# input1-9.net
KiCad netlist of a schematic drawn in Altium Designer
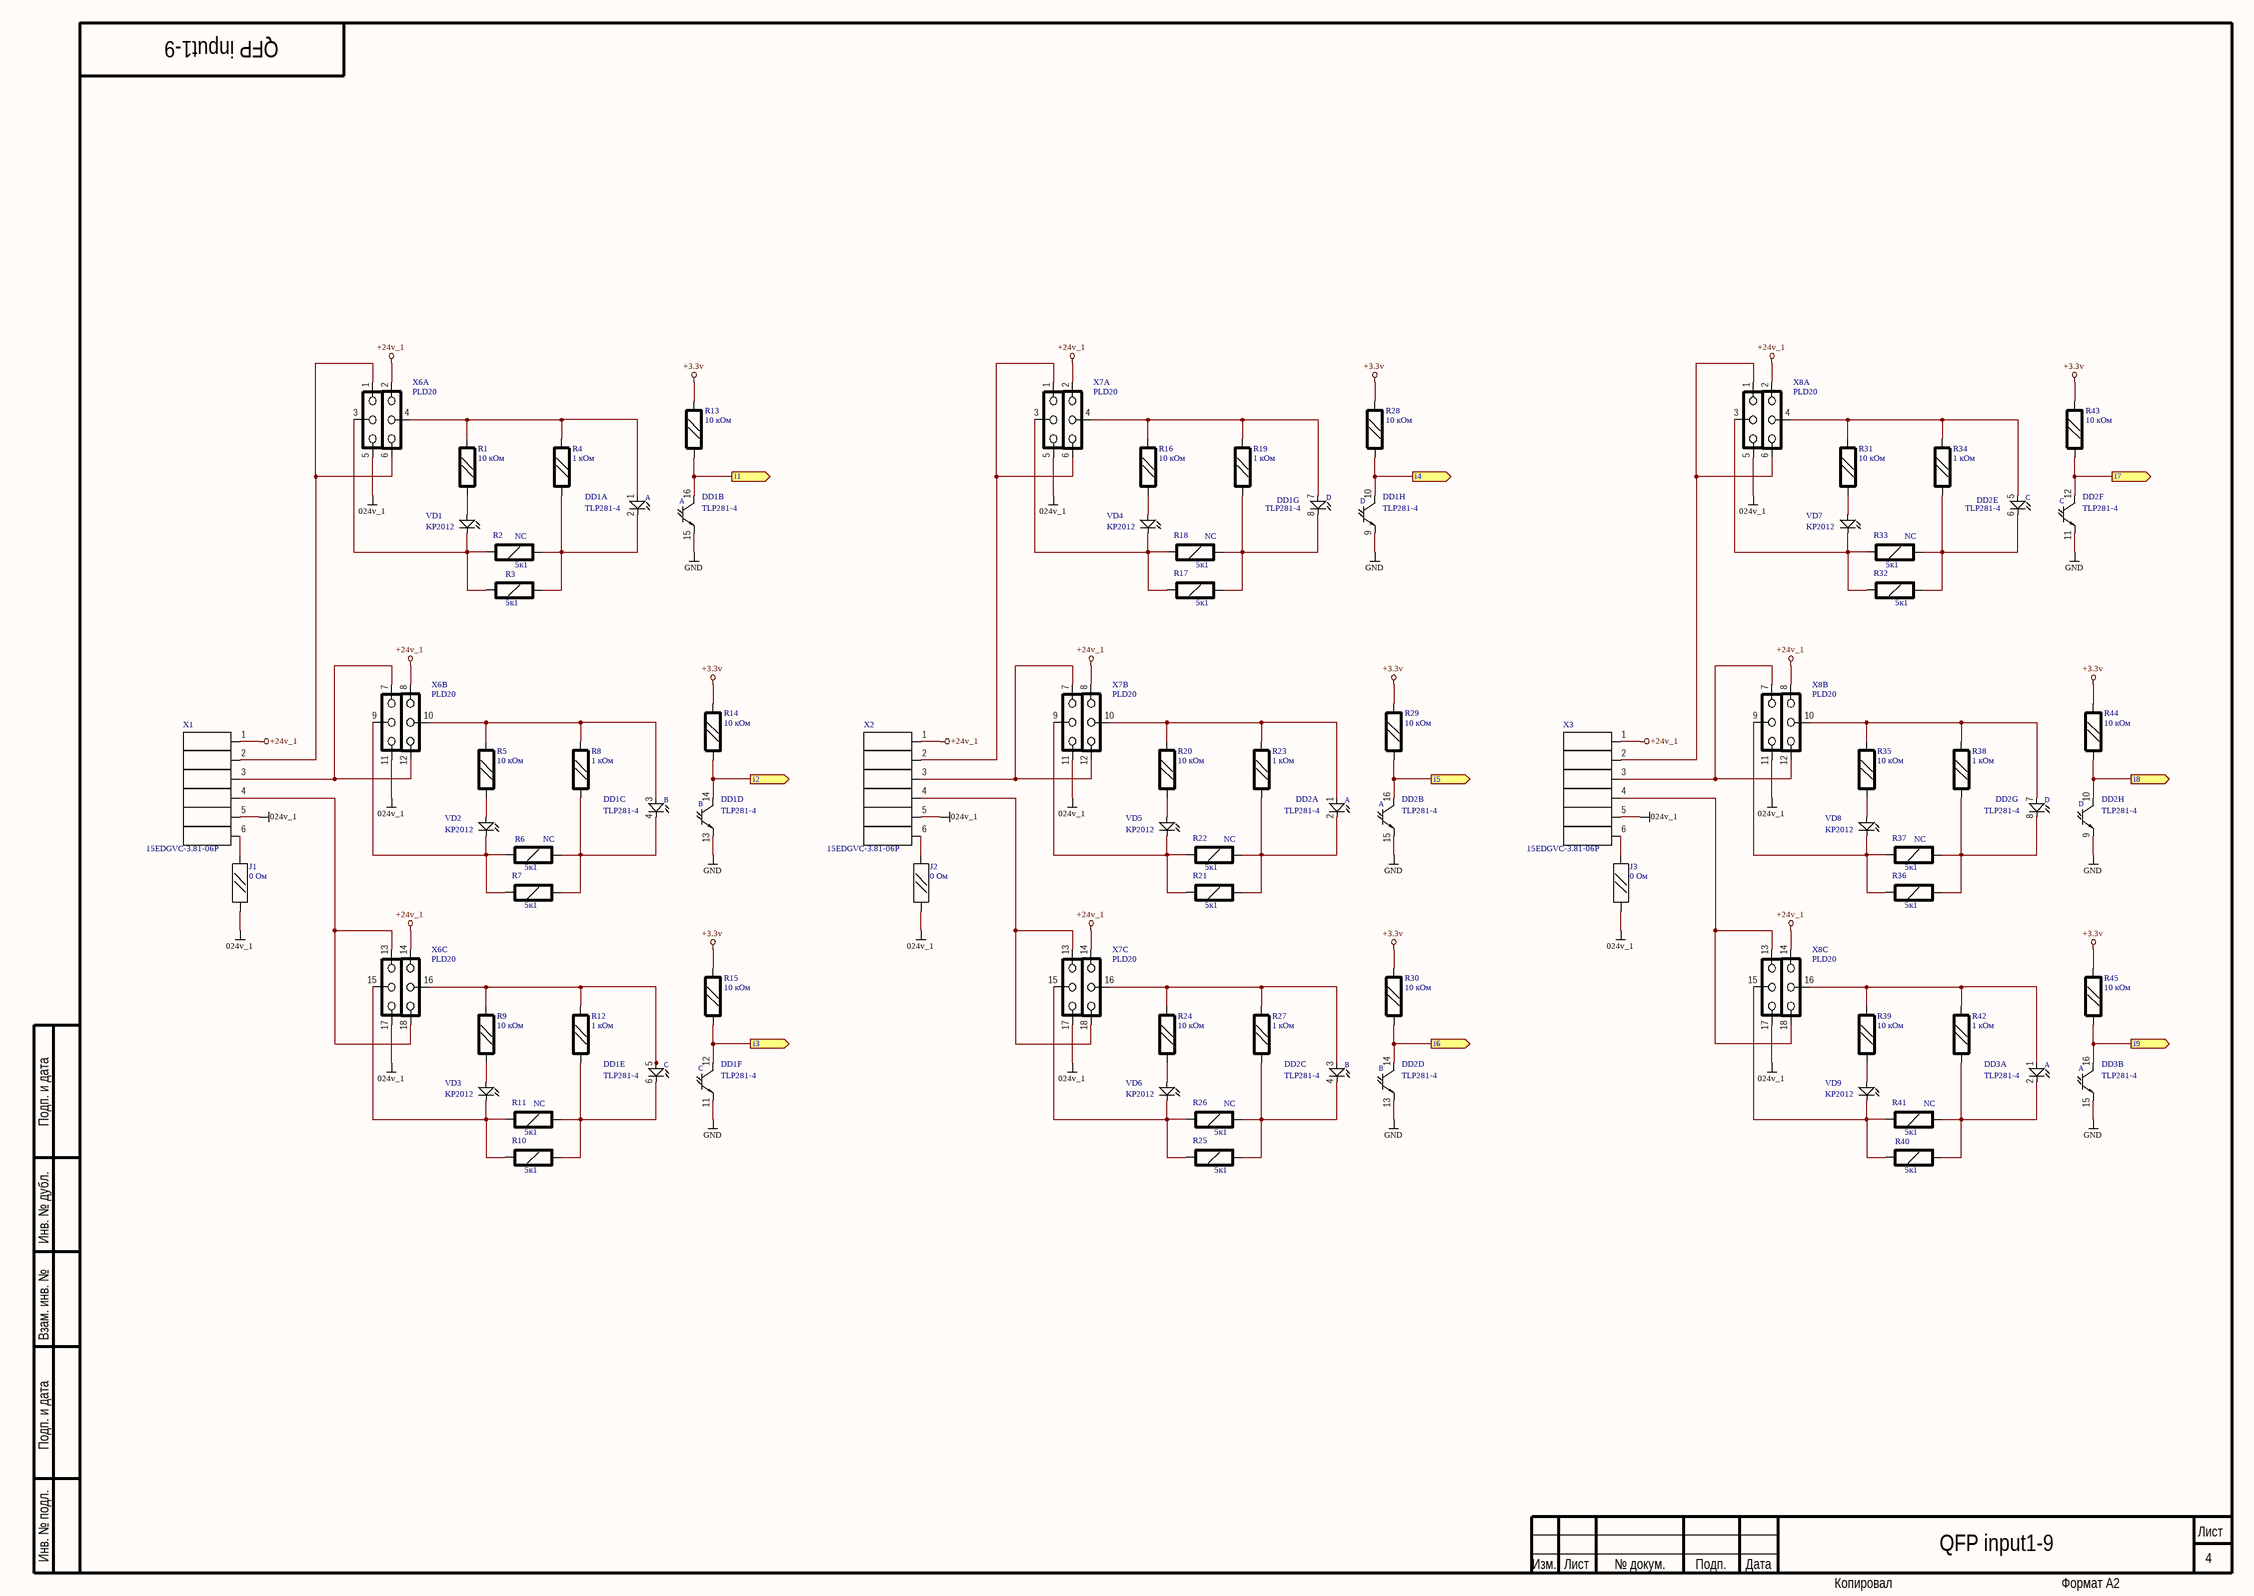
[diagram p0: input1-9.SchDoc]

(export (version "E")
  (design (tool "Eeschema 10.0.6"))
  (components
    (comp (ref "DD1")
      (value "TLP281-4")
      (footprint "SO16")
      (description "4х канальная транзисторная оптопара")
      (fields (field (name "VOLTAGE") "80V"))
      (libsource (lib "L02_22F") (part "TLP281-4"))
    )
    (comp (ref "DD2")
      (value "TLP281-4")
      (footprint "SO16")
      (description "4х канальная транзисторная оптопара")
      (fields (field (name "VOLTAGE") "80V"))
      (libsource (lib "L02_22F") (part "TLP281-4"))
    )
    (comp (ref "DD3")
      (value "TLP281-4")
      (footprint "SO16")
      (description "4х канальная транзисторная оптопара")
      (fields (field (name "VOLTAGE") "80V"))
      (libsource (lib "L02_22F") (part "TLP281-4"))
    )
    (comp (ref "J1")
      (value "0 Ом")
      (footprint "SMD0805RES")
      (description "SMD 0805 перемычка")
      (libsource (lib "iL03_22") (part "JR0805"))
    )
    (comp (ref "J2")
      (value "0 Ом")
      (footprint "SMD0805RES")
      (description "SMD 0805 перемычка")
      (libsource (lib "iL03_22") (part "JR0805"))
    )
    (comp (ref "J3")
      (value "0 Ом")
      (footprint "SMD0805RES")
      (description "SMD 0805 перемычка")
      (libsource (lib "iL03_22") (part "JR0805"))
    )
    (comp (ref "R1")
      (value "10 кОм")
      (footprint "SMD0805RES")
      (description "Чип резистор 0805")
      (fields (field (name "TOLERANCE") "5%"))
      (libsource (lib "SL02_22F") (part "R0805"))
    )
    (comp (ref "R2")
      (value "5к1")
      (footprint "RES1206")
      (description "Чип резистор 1206")
      (fields (field (name "TOLERANCE") "5%") (field (name "SOLDEROPTON") "NC"))
      (libsource (lib "SL02_22F") (part "R1206"))
    )
    (comp (ref "R3")
      (value "5к1")
      (footprint "RES1206")
      (description "Чип резистор 1206")
      (fields (field (name "TOLERANCE") "5%"))
      (libsource (lib "SL02_22F") (part "R1206"))
    )
    (comp (ref "R4")
      (value "1 кОм")
      (footprint "SMD0805RES")
      (description "Чип резистор 0805")
      (fields (field (name "TOLERANCE") "5%"))
      (libsource (lib "SL02_22F") (part "R0805"))
    )
    (comp (ref "R5")
      (value "10 кОм")
      (footprint "SMD0805RES")
      (description "Чип резистор 0805")
      (fields (field (name "TOLERANCE") "5%"))
      (libsource (lib "SL02_22F") (part "R0805"))
    )
    (comp (ref "R6")
      (value "5к1")
      (footprint "RES1206")
      (description "Чип резистор 1206")
      (fields (field (name "TOLERANCE") "5%") (field (name "SOLDEROPTON") "NC"))
      (libsource (lib "SL02_22F") (part "R1206"))
    )
    (comp (ref "R7")
      (value "5к1")
      (footprint "RES1206")
      (description "Чип резистор 1206")
      (fields (field (name "TOLERANCE") "5%"))
      (libsource (lib "SL02_22F") (part "R1206"))
    )
    (comp (ref "R8")
      (value "1 кОм")
      (footprint "SMD0805RES")
      (description "Чип резистор 0805")
      (fields (field (name "TOLERANCE") "5%"))
      (libsource (lib "SL02_22F") (part "R0805"))
    )
    (comp (ref "R9")
      (value "10 кОм")
      (footprint "SMD0805RES")
      (description "Чип резистор 0805")
      (fields (field (name "TOLERANCE") "5%"))
      (libsource (lib "SL02_22F") (part "R0805"))
    )
    (comp (ref "R10")
      (value "5к1")
      (footprint "RES1206")
      (description "Чип резистор 1206")
      (fields (field (name "TOLERANCE") "5%"))
      (libsource (lib "SL02_22F") (part "R1206"))
    )
    (comp (ref "R11")
      (value "5к1")
      (footprint "RES1206")
      (description "Чип резистор 1206")
      (fields (field (name "TOLERANCE") "5%") (field (name "SOLDEROPTON") "NC"))
      (libsource (lib "SL02_22F") (part "R1206"))
    )
    (comp (ref "R12")
      (value "1 кОм")
      (footprint "SMD0805RES")
      (description "Чип резистор 0805")
      (fields (field (name "TOLERANCE") "5%"))
      (libsource (lib "SL02_22F") (part "R0805"))
    )
    (comp (ref "R13")
      (value "10 кОм")
      (footprint "SMD0805RES")
      (description "Чип резистор 0805")
      (fields (field (name "TOLERANCE") "5%"))
      (libsource (lib "SL02_22F") (part "R0805"))
    )
    (comp (ref "R14")
      (value "10 кОм")
      (footprint "SMD0805RES")
      (description "Чип резистор 0805")
      (fields (field (name "TOLERANCE") "5%"))
      (libsource (lib "SL02_22F") (part "R0805"))
    )
    (comp (ref "R15")
      (value "10 кОм")
      (footprint "SMD0805RES")
      (description "Чип резистор 0805")
      (fields (field (name "TOLERANCE") "5%"))
      (libsource (lib "SL02_22F") (part "R0805"))
    )
    (comp (ref "R16")
      (value "10 кОм")
      (footprint "SMD0805RES")
      (description "Чип резистор 0805")
      (fields (field (name "TOLERANCE") "5%"))
      (libsource (lib "SL02_22F") (part "R0805"))
    )
    (comp (ref "R17")
      (value "5к1")
      (footprint "RES1206")
      (description "Чип резистор 1206")
      (fields (field (name "TOLERANCE") "5%"))
      (libsource (lib "SL02_22F") (part "R1206"))
    )
    (comp (ref "R18")
      (value "5к1")
      (footprint "RES1206")
      (description "Чип резистор 1206")
      (fields (field (name "TOLERANCE") "5%") (field (name "SOLDEROPTON") "NC"))
      (libsource (lib "SL02_22F") (part "R1206"))
    )
    (comp (ref "R19")
      (value "1 кОм")
      (footprint "SMD0805RES")
      (description "Чип резистор 0805")
      (fields (field (name "TOLERANCE") "5%"))
      (libsource (lib "SL02_22F") (part "R0805"))
    )
    (comp (ref "R20")
      (value "10 кОм")
      (footprint "SMD0805RES")
      (description "Чип резистор 0805")
      (fields (field (name "TOLERANCE") "5%"))
      (libsource (lib "SL02_22F") (part "R0805"))
    )
    (comp (ref "R21")
      (value "5к1")
      (footprint "RES1206")
      (description "Чип резистор 1206")
      (fields (field (name "TOLERANCE") "5%"))
      (libsource (lib "SL02_22F") (part "R1206"))
    )
    (comp (ref "R22")
      (value "5к1")
      (footprint "RES1206")
      (description "Чип резистор 1206")
      (fields (field (name "TOLERANCE") "5%") (field (name "SOLDEROPTON") "NC"))
      (libsource (lib "SL02_22F") (part "R1206"))
    )
    (comp (ref "R23")
      (value "1 кОм")
      (footprint "SMD0805RES")
      (description "Чип резистор 0805")
      (fields (field (name "TOLERANCE") "5%"))
      (libsource (lib "SL02_22F") (part "R0805"))
    )
    (comp (ref "R24")
      (value "10 кОм")
      (footprint "SMD0805RES")
      (description "Чип резистор 0805")
      (fields (field (name "TOLERANCE") "5%"))
      (libsource (lib "SL02_22F") (part "R0805"))
    )
    (comp (ref "R25")
      (value "5к1")
      (footprint "RES1206")
      (description "Чип резистор 1206")
      (fields (field (name "TOLERANCE") "5%"))
      (libsource (lib "SL02_22F") (part "R1206"))
    )
    (comp (ref "R26")
      (value "5к1")
      (footprint "RES1206")
      (description "Чип резистор 1206")
      (fields (field (name "TOLERANCE") "5%") (field (name "SOLDEROPTON") "NC"))
      (libsource (lib "SL02_22F") (part "R1206"))
    )
    (comp (ref "R27")
      (value "1 кОм")
      (footprint "SMD0805RES")
      (description "Чип резистор 0805")
      (fields (field (name "TOLERANCE") "5%"))
      (libsource (lib "SL02_22F") (part "R0805"))
    )
    (comp (ref "R28")
      (value "10 кОм")
      (footprint "SMD0805RES")
      (description "Чип резистор 0805")
      (fields (field (name "TOLERANCE") "5%"))
      (libsource (lib "SL02_22F") (part "R0805"))
    )
    (comp (ref "R29")
      (value "10 кОм")
      (footprint "SMD0805RES")
      (description "Чип резистор 0805")
      (fields (field (name "TOLERANCE") "5%"))
      (libsource (lib "SL02_22F") (part "R0805"))
    )
    (comp (ref "R30")
      (value "10 кОм")
      (footprint "SMD0805RES")
      (description "Чип резистор 0805")
      (fields (field (name "TOLERANCE") "5%"))
      (libsource (lib "SL02_22F") (part "R0805"))
    )
    (comp (ref "R31")
      (value "10 кОм")
      (footprint "SMD0805RES")
      (description "Чип резистор 0805")
      (fields (field (name "TOLERANCE") "5%"))
      (libsource (lib "SL02_22F") (part "R0805"))
    )
    (comp (ref "R32")
      (value "5к1")
      (footprint "RES1206")
      (description "Чип резистор 1206")
      (fields (field (name "TOLERANCE") "5%"))
      (libsource (lib "SL02_22F") (part "R1206"))
    )
    (comp (ref "R33")
      (value "5к1")
      (footprint "RES1206")
      (description "Чип резистор 1206")
      (fields (field (name "TOLERANCE") "5%") (field (name "SOLDEROPTON") "NC"))
      (libsource (lib "SL02_22F") (part "R1206"))
    )
    (comp (ref "R34")
      (value "1 кОм")
      (footprint "SMD0805RES")
      (description "Чип резистор 0805")
      (fields (field (name "TOLERANCE") "5%"))
      (libsource (lib "SL02_22F") (part "R0805"))
    )
    (comp (ref "R35")
      (value "10 кОм")
      (footprint "SMD0805RES")
      (description "Чип резистор 0805")
      (fields (field (name "TOLERANCE") "5%"))
      (libsource (lib "SL02_22F") (part "R0805"))
    )
    (comp (ref "R36")
      (value "5к1")
      (footprint "RES1206")
      (description "Чип резистор 1206")
      (fields (field (name "TOLERANCE") "5%"))
      (libsource (lib "SL02_22F") (part "R1206"))
    )
    (comp (ref "R37")
      (value "5к1")
      (footprint "RES1206")
      (description "Чип резистор 1206")
      (fields (field (name "TOLERANCE") "5%") (field (name "SOLDEROPTON") "NC"))
      (libsource (lib "SL02_22F") (part "R1206"))
    )
    (comp (ref "R38")
      (value "1 кОм")
      (footprint "SMD0805RES")
      (description "Чип резистор 0805")
      (fields (field (name "TOLERANCE") "5%"))
      (libsource (lib "SL02_22F") (part "R0805"))
    )
    (comp (ref "R39")
      (value "10 кОм")
      (footprint "SMD0805RES")
      (description "Чип резистор 0805")
      (fields (field (name "TOLERANCE") "5%"))
      (libsource (lib "SL02_22F") (part "R0805"))
    )
    (comp (ref "R40")
      (value "5к1")
      (footprint "RES1206")
      (description "Чип резистор 1206")
      (fields (field (name "TOLERANCE") "5%"))
      (libsource (lib "SL02_22F") (part "R1206"))
    )
    (comp (ref "R41")
      (value "5к1")
      (footprint "RES1206")
      (description "Чип резистор 1206")
      (fields (field (name "TOLERANCE") "5%") (field (name "SOLDEROPTON") "NC"))
      (libsource (lib "SL02_22F") (part "R1206"))
    )
    (comp (ref "R42")
      (value "1 кОм")
      (footprint "SMD0805RES")
      (description "Чип резистор 0805")
      (fields (field (name "TOLERANCE") "5%"))
      (libsource (lib "SL02_22F") (part "R0805"))
    )
    (comp (ref "R43")
      (value "10 кОм")
      (footprint "SMD0805RES")
      (description "Чип резистор 0805")
      (fields (field (name "TOLERANCE") "5%"))
      (libsource (lib "SL02_22F") (part "R0805"))
    )
    (comp (ref "R44")
      (value "10 кОм")
      (footprint "SMD0805RES")
      (description "Чип резистор 0805")
      (fields (field (name "TOLERANCE") "5%"))
      (libsource (lib "SL02_22F") (part "R0805"))
    )
    (comp (ref "R45")
      (value "10 кОм")
      (footprint "SMD0805RES")
      (description "Чип резистор 0805")
      (fields (field (name "TOLERANCE") "5%"))
      (libsource (lib "SL02_22F") (part "R0805"))
    )
    (comp (ref "VD1")
      (value "KP2012")
      (footprint "SMD0805DIO_C")
      (description "Чип светодиод 0805")
      (libsource (lib "L02_22F") (part "KP2012_C"))
    )
    (comp (ref "VD2")
      (value "KP2012")
      (footprint "SMD0805DIO_C")
      (description "Чип светодиод 0805")
      (libsource (lib "L02_22F") (part "KP2012_C"))
    )
    (comp (ref "VD3")
      (value "KP2012")
      (footprint "SMD0805DIO_C")
      (description "Чип светодиод 0805")
      (libsource (lib "L02_22F") (part "KP2012_C"))
    )
    (comp (ref "VD4")
      (value "KP2012")
      (footprint "SMD0805DIO_C")
      (description "Чип светодиод 0805")
      (libsource (lib "L02_22F") (part "KP2012_C"))
    )
    (comp (ref "VD5")
      (value "KP2012")
      (footprint "SMD0805DIO_C")
      (description "Чип светодиод 0805")
      (libsource (lib "L02_22F") (part "KP2012_C"))
    )
    (comp (ref "VD6")
      (value "KP2012")
      (footprint "SMD0805DIO_C")
      (description "Чип светодиод 0805")
      (libsource (lib "L02_22F") (part "KP2012_C"))
    )
    (comp (ref "VD7")
      (value "KP2012")
      (footprint "SMD0805DIO_C")
      (description "Чип светодиод 0805")
      (libsource (lib "L02_22F") (part "KP2012_C"))
    )
    (comp (ref "VD8")
      (value "KP2012")
      (footprint "SMD0805DIO_C")
      (description "Чип светодиод 0805")
      (libsource (lib "L02_22F") (part "KP2012_C"))
    )
    (comp (ref "VD9")
      (value "KP2012")
      (footprint "SMD0805DIO_C")
      (description "Чип светодиод 0805")
      (libsource (lib "L02_22F") (part "KP2012_C"))
    )
    (comp (ref "X1")
      (value "15EDGVC-3.81-06P")
      (footprint "15EDGVC_081_6")
      (description "Вилка  6/3.81")
      (fields (field (name "VOLTAGE") "2кВ"))
      (libsource (lib "L02_22F") (part "15EDGVC-3.81-06P"))
    )
    (comp (ref "X2")
      (value "15EDGVC-3.81-06P")
      (footprint "15EDGVC_081_6")
      (description "Вилка  6/3.81")
      (fields (field (name "VOLTAGE") "2кВ"))
      (libsource (lib "L02_22F") (part "15EDGVC-3.81-06P"))
    )
    (comp (ref "X3")
      (value "15EDGVC-3.81-06P")
      (footprint "15EDGVC_081_6")
      (description "Вилка  6/3.81")
      (fields (field (name "VOLTAGE") "2кВ"))
      (libsource (lib "L02_22F") (part "15EDGVC-3.81-06P"))
    )
    (comp (ref "X6")
      (value "PLD20")
      (footprint "pld2x10_1.27")
      (description "Вилка  PLD 20/1.27")
      (libsource (lib "SL02_22F") (part "PLD20"))
    )
    (comp (ref "X7")
      (value "PLD20")
      (footprint "pld2x10_1.27")
      (description "Вилка  PLD 20/1.27")
      (libsource (lib "SL02_22F") (part "PLD20"))
    )
    (comp (ref "X8")
      (value "PLD20")
      (footprint "pld2x10_1.27")
      (description "Вилка  PLD 20/1.27")
      (libsource (lib "SL02_22F") (part "PLD20"))
    )
  )
  (nets
    (net (code "1") (name "+3.3v") (class "Default")
      (node (ref "R13") (pin "2") (pinfunction "2_2") (pintype "passive"))
      (node (ref "R14") (pin "2") (pinfunction "2_2") (pintype "passive"))
      (node (ref "R15") (pin "2") (pinfunction "2_2") (pintype "passive"))
      (node (ref "R28") (pin "2") (pinfunction "2_2") (pintype "passive"))
      (node (ref "R29") (pin "2") (pinfunction "2_2") (pintype "passive"))
      (node (ref "R30") (pin "2") (pinfunction "2_2") (pintype "passive"))
      (node (ref "R43") (pin "2") (pinfunction "2_2") (pintype "passive"))
      (node (ref "R44") (pin "2") (pinfunction "2_2") (pintype "passive"))
      (node (ref "R45") (pin "2") (pinfunction "2_2") (pintype "passive"))
    )
    (net (code "2") (name "+24v_1") (class "Default")
      (node (ref "X1") (pin "1") (pinfunction "1_1") (pintype "passive"))
      (node (ref "X2") (pin "1") (pinfunction "1_1") (pintype "passive"))
      (node (ref "X3") (pin "1") (pinfunction "1_1") (pintype "passive"))
      (node (ref "X6") (pin "14") (pinfunction "14_14") (pintype "passive"))
      (node (ref "X6") (pin "2") (pinfunction "2_2") (pintype "passive"))
      (node (ref "X6") (pin "8") (pinfunction "8_8") (pintype "passive"))
      (node (ref "X7") (pin "14") (pinfunction "14_14") (pintype "passive"))
      (node (ref "X7") (pin "2") (pinfunction "2_2") (pintype "passive"))
      (node (ref "X7") (pin "8") (pinfunction "8_8") (pintype "passive"))
      (node (ref "X8") (pin "14") (pinfunction "14_14") (pintype "passive"))
      (node (ref "X8") (pin "2") (pinfunction "2_2") (pintype "passive"))
      (node (ref "X8") (pin "8") (pinfunction "8_8") (pintype "passive"))
    )
    (net (code "3") (name "/i1") (class "Default")
      (node (ref "DD1") (pin "16") (pinfunction "Collector_A_16") (pintype "passive"))
      (node (ref "R13") (pin "1") (pinfunction "1_1") (pintype "passive"))
    )
    (net (code "4") (name "/i2") (class "Default")
      (node (ref "DD1") (pin "14") (pinfunction "Collector_B_14") (pintype "passive"))
      (node (ref "R14") (pin "1") (pinfunction "1_1") (pintype "passive"))
    )
    (net (code "5") (name "/i3") (class "Default")
      (node (ref "DD1") (pin "12") (pinfunction "Collector_C_12") (pintype "passive"))
      (node (ref "R15") (pin "1") (pinfunction "1_1") (pintype "passive"))
    )
    (net (code "6") (name "/i4") (class "Default")
      (node (ref "DD1") (pin "10") (pinfunction "Collector_D_10") (pintype "passive"))
      (node (ref "R28") (pin "1") (pinfunction "1_1") (pintype "passive"))
    )
    (net (code "7") (name "/i5") (class "Default")
      (node (ref "DD2") (pin "16") (pinfunction "Collector_A_16") (pintype "passive"))
      (node (ref "R29") (pin "1") (pinfunction "1_1") (pintype "passive"))
    )
    (net (code "8") (name "/i6") (class "Default")
      (node (ref "DD2") (pin "14") (pinfunction "Collector_B_14") (pintype "passive"))
      (node (ref "R30") (pin "1") (pinfunction "1_1") (pintype "passive"))
    )
    (net (code "9") (name "/i7") (class "Default")
      (node (ref "DD2") (pin "12") (pinfunction "Collector_C_12") (pintype "passive"))
      (node (ref "R43") (pin "1") (pinfunction "1_1") (pintype "passive"))
    )
    (net (code "10") (name "/i8") (class "Default")
      (node (ref "DD2") (pin "10") (pinfunction "Collector_D_10") (pintype "passive"))
      (node (ref "R44") (pin "1") (pinfunction "1_1") (pintype "passive"))
    )
    (net (code "11") (name "/i9") (class "Default")
      (node (ref "DD3") (pin "16") (pinfunction "Collector_A_16") (pintype "passive"))
      (node (ref "R45") (pin "1") (pinfunction "1_1") (pintype "passive"))
    )
    (net (code "12") (name "024v_1") (class "Default")
      (node (ref "J1") (pin "1") (pinfunction "1_1") (pintype "passive"))
      (node (ref "J2") (pin "2") (pinfunction "2_2") (pintype "passive"))
      (node (ref "J3") (pin "2") (pinfunction "2_2") (pintype "passive"))
      (node (ref "X1") (pin "5") (pinfunction "5_5") (pintype "passive"))
      (node (ref "X2") (pin "5") (pinfunction "5_5") (pintype "passive"))
      (node (ref "X3") (pin "5") (pinfunction "5_5") (pintype "passive"))
      (node (ref "X6") (pin "11") (pinfunction "11_11") (pintype "passive"))
      (node (ref "X6") (pin "17") (pinfunction "17_17") (pintype "passive"))
      (node (ref "X6") (pin "5") (pinfunction "5_5") (pintype "passive"))
      (node (ref "X7") (pin "11") (pinfunction "11_11") (pintype "passive"))
      (node (ref "X7") (pin "17") (pinfunction "17_17") (pintype "passive"))
      (node (ref "X7") (pin "5") (pinfunction "5_5") (pintype "passive"))
      (node (ref "X8") (pin "11") (pinfunction "11_11") (pintype "passive"))
      (node (ref "X8") (pin "17") (pinfunction "17_17") (pintype "passive"))
      (node (ref "X8") (pin "5") (pinfunction "5_5") (pintype "passive"))
    )
    (net (code "13") (name "GND") (class "Default")
      (node (ref "DD1") (pin "11") (pinfunction "Emitter_C_11") (pintype "passive"))
      (node (ref "DD1") (pin "13") (pinfunction "Emitter_B_13") (pintype "passive"))
      (node (ref "DD1") (pin "15") (pinfunction "Emitter_A_15") (pintype "passive"))
      (node (ref "DD1") (pin "9") (pinfunction "Emitter_D_9") (pintype "passive"))
      (node (ref "DD2") (pin "11") (pinfunction "Emitter_C_11") (pintype "passive"))
      (node (ref "DD2") (pin "13") (pinfunction "Emitter_B_13") (pintype "passive"))
      (node (ref "DD2") (pin "15") (pinfunction "Emitter_A_15") (pintype "passive"))
      (node (ref "DD2") (pin "9") (pinfunction "Emitter_D_9") (pintype "passive"))
      (node (ref "DD3") (pin "15") (pinfunction "Emitter_A_15") (pintype "passive"))
    )
    (net (code "14") (name "Net-(DD1A-Anode_A)") (class "Default")
      (node (ref "DD1") (pin "1") (pinfunction "Anode_A_1") (pintype "passive"))
      (node (ref "R1") (pin "1") (pinfunction "1_1") (pintype "passive"))
      (node (ref "R4") (pin "1") (pinfunction "1_1") (pintype "passive"))
      (node (ref "X6") (pin "4") (pinfunction "4_4") (pintype "passive"))
    )
    (net (code "15") (name "Net-(DD1A-Cathode_A)") (class "Default")
      (node (ref "DD1") (pin "2") (pinfunction "Cathode_A_2") (pintype "passive"))
      (node (ref "R2") (pin "2") (pinfunction "2_2") (pintype "passive"))
      (node (ref "R3") (pin "2") (pinfunction "2_2") (pintype "passive"))
      (node (ref "R4") (pin "2") (pinfunction "2_2") (pintype "passive"))
    )
    (net (code "16") (name "Net-(DD1C-Anode_B)") (class "Default")
      (node (ref "DD1") (pin "3") (pinfunction "Anode_B_3") (pintype "passive"))
      (node (ref "R5") (pin "1") (pinfunction "1_1") (pintype "passive"))
      (node (ref "R8") (pin "1") (pinfunction "1_1") (pintype "passive"))
      (node (ref "X6") (pin "10") (pinfunction "10_10") (pintype "passive"))
    )
    (net (code "17") (name "Net-(DD1C-Cathode_B)") (class "Default")
      (node (ref "DD1") (pin "4") (pinfunction "Cathode_B_4") (pintype "passive"))
      (node (ref "R6") (pin "2") (pinfunction "2_2") (pintype "passive"))
      (node (ref "R7") (pin "2") (pinfunction "2_2") (pintype "passive"))
      (node (ref "R8") (pin "2") (pinfunction "2_2") (pintype "passive"))
    )
    (net (code "18") (name "Net-(DD1E-Anode_C)") (class "Default")
      (node (ref "DD1") (pin "5") (pinfunction "Anode_C_5") (pintype "passive"))
      (node (ref "R12") (pin "1") (pinfunction "1_1") (pintype "passive"))
      (node (ref "R9") (pin "1") (pinfunction "1_1") (pintype "passive"))
      (node (ref "X6") (pin "16") (pinfunction "16_16") (pintype "passive"))
    )
    (net (code "19") (name "Net-(DD1E-Cathode)") (class "Default")
      (node (ref "DD1") (pin "6") (pinfunction "Cathode_6") (pintype "passive"))
      (node (ref "R10") (pin "2") (pinfunction "2_2") (pintype "passive"))
      (node (ref "R11") (pin "2") (pinfunction "2_2") (pintype "passive"))
      (node (ref "R12") (pin "2") (pinfunction "2_2") (pintype "passive"))
    )
    (net (code "20") (name "Net-(DD1G-Anode_D)") (class "Default")
      (node (ref "DD1") (pin "7") (pinfunction "Anode_D_7") (pintype "passive"))
      (node (ref "R16") (pin "1") (pinfunction "1_1") (pintype "passive"))
      (node (ref "R19") (pin "1") (pinfunction "1_1") (pintype "passive"))
      (node (ref "X7") (pin "4") (pinfunction "4_4") (pintype "passive"))
    )
    (net (code "21") (name "Net-(DD1G-Cathode_D)") (class "Default")
      (node (ref "DD1") (pin "8") (pinfunction "Cathode_D_8") (pintype "passive"))
      (node (ref "R17") (pin "2") (pinfunction "2_2") (pintype "passive"))
      (node (ref "R18") (pin "2") (pinfunction "2_2") (pintype "passive"))
      (node (ref "R19") (pin "2") (pinfunction "2_2") (pintype "passive"))
    )
    (net (code "22") (name "Net-(DD2A-Anode_A)") (class "Default")
      (node (ref "DD2") (pin "1") (pinfunction "Anode_A_1") (pintype "passive"))
      (node (ref "R20") (pin "1") (pinfunction "1_1") (pintype "passive"))
      (node (ref "R23") (pin "1") (pinfunction "1_1") (pintype "passive"))
      (node (ref "X7") (pin "10") (pinfunction "10_10") (pintype "passive"))
    )
    (net (code "23") (name "Net-(DD2A-Cathode_A)") (class "Default")
      (node (ref "DD2") (pin "2") (pinfunction "Cathode_A_2") (pintype "passive"))
      (node (ref "R21") (pin "2") (pinfunction "2_2") (pintype "passive"))
      (node (ref "R22") (pin "2") (pinfunction "2_2") (pintype "passive"))
      (node (ref "R23") (pin "2") (pinfunction "2_2") (pintype "passive"))
    )
    (net (code "24") (name "Net-(DD2C-Anode_B)") (class "Default")
      (node (ref "DD2") (pin "3") (pinfunction "Anode_B_3") (pintype "passive"))
      (node (ref "R24") (pin "1") (pinfunction "1_1") (pintype "passive"))
      (node (ref "R27") (pin "1") (pinfunction "1_1") (pintype "passive"))
      (node (ref "X7") (pin "16") (pinfunction "16_16") (pintype "passive"))
    )
    (net (code "25") (name "Net-(DD2C-Cathode_B)") (class "Default")
      (node (ref "DD2") (pin "4") (pinfunction "Cathode_B_4") (pintype "passive"))
      (node (ref "R25") (pin "2") (pinfunction "2_2") (pintype "passive"))
      (node (ref "R26") (pin "2") (pinfunction "2_2") (pintype "passive"))
      (node (ref "R27") (pin "2") (pinfunction "2_2") (pintype "passive"))
    )
    (net (code "26") (name "Net-(DD2E-Anode_C)") (class "Default")
      (node (ref "DD2") (pin "5") (pinfunction "Anode_C_5") (pintype "passive"))
      (node (ref "R31") (pin "1") (pinfunction "1_1") (pintype "passive"))
      (node (ref "R34") (pin "1") (pinfunction "1_1") (pintype "passive"))
      (node (ref "X8") (pin "4") (pinfunction "4_4") (pintype "passive"))
    )
    (net (code "27") (name "Net-(DD2E-Cathode)") (class "Default")
      (node (ref "DD2") (pin "6") (pinfunction "Cathode_6") (pintype "passive"))
      (node (ref "R32") (pin "2") (pinfunction "2_2") (pintype "passive"))
      (node (ref "R33") (pin "2") (pinfunction "2_2") (pintype "passive"))
      (node (ref "R34") (pin "2") (pinfunction "2_2") (pintype "passive"))
    )
    (net (code "28") (name "Net-(DD2G-Anode_D)") (class "Default")
      (node (ref "DD2") (pin "7") (pinfunction "Anode_D_7") (pintype "passive"))
      (node (ref "R35") (pin "1") (pinfunction "1_1") (pintype "passive"))
      (node (ref "R38") (pin "1") (pinfunction "1_1") (pintype "passive"))
      (node (ref "X8") (pin "10") (pinfunction "10_10") (pintype "passive"))
    )
    (net (code "29") (name "Net-(DD2G-Cathode_D)") (class "Default")
      (node (ref "DD2") (pin "8") (pinfunction "Cathode_D_8") (pintype "passive"))
      (node (ref "R36") (pin "2") (pinfunction "2_2") (pintype "passive"))
      (node (ref "R37") (pin "2") (pinfunction "2_2") (pintype "passive"))
      (node (ref "R38") (pin "2") (pinfunction "2_2") (pintype "passive"))
    )
    (net (code "30") (name "Net-(DD3A-Anode_A)") (class "Default")
      (node (ref "DD3") (pin "1") (pinfunction "Anode_A_1") (pintype "passive"))
      (node (ref "R39") (pin "1") (pinfunction "1_1") (pintype "passive"))
      (node (ref "R42") (pin "1") (pinfunction "1_1") (pintype "passive"))
      (node (ref "X8") (pin "16") (pinfunction "16_16") (pintype "passive"))
    )
    (net (code "31") (name "Net-(DD3A-Cathode_A)") (class "Default")
      (node (ref "DD3") (pin "2") (pinfunction "Cathode_A_2") (pintype "passive"))
      (node (ref "R40") (pin "2") (pinfunction "2_2") (pintype "passive"))
      (node (ref "R41") (pin "2") (pinfunction "2_2") (pintype "passive"))
      (node (ref "R42") (pin "2") (pinfunction "2_2") (pintype "passive"))
    )
    (net (code "32") (name "Net-(J1-Pad2)") (class "Default")
      (node (ref "J1") (pin "2") (pinfunction "2_2") (pintype "passive"))
      (node (ref "X1") (pin "6") (pinfunction "6_6") (pintype "passive"))
    )
    (net (code "33") (name "Net-(J2-Pad1)") (class "Default")
      (node (ref "J2") (pin "1") (pinfunction "1_1") (pintype "passive"))
      (node (ref "X2") (pin "6") (pinfunction "6_6") (pintype "passive"))
    )
    (net (code "34") (name "Net-(J3-Pad1)") (class "Default")
      (node (ref "J3") (pin "1") (pinfunction "1_1") (pintype "passive"))
      (node (ref "X3") (pin "6") (pinfunction "6_6") (pintype "passive"))
    )
    (net (code "35") (name "Net-(VD1-Anode)") (class "Default")
      (node (ref "R1") (pin "2") (pinfunction "2_2") (pintype "passive"))
      (node (ref "VD1") (pin "2") (pinfunction "Anode_2") (pintype "passive"))
    )
    (net (code "36") (name "Net-(VD1-Cathode)") (class "Default")
      (node (ref "R2") (pin "1") (pinfunction "1_1") (pintype "passive"))
      (node (ref "R3") (pin "1") (pinfunction "1_1") (pintype "passive"))
      (node (ref "VD1") (pin "1") (pinfunction "Cathode_1") (pintype "passive"))
      (node (ref "X6") (pin "3") (pinfunction "3_3") (pintype "passive"))
    )
    (net (code "37") (name "Net-(VD2-Anode)") (class "Default")
      (node (ref "R5") (pin "2") (pinfunction "2_2") (pintype "passive"))
      (node (ref "VD2") (pin "2") (pinfunction "Anode_2") (pintype "passive"))
    )
    (net (code "38") (name "Net-(VD2-Cathode)") (class "Default")
      (node (ref "R6") (pin "1") (pinfunction "1_1") (pintype "passive"))
      (node (ref "R7") (pin "1") (pinfunction "1_1") (pintype "passive"))
      (node (ref "VD2") (pin "1") (pinfunction "Cathode_1") (pintype "passive"))
      (node (ref "X6") (pin "9") (pinfunction "9_9") (pintype "passive"))
    )
    (net (code "39") (name "Net-(VD3-Anode)") (class "Default")
      (node (ref "R9") (pin "2") (pinfunction "2_2") (pintype "passive"))
      (node (ref "VD3") (pin "2") (pinfunction "Anode_2") (pintype "passive"))
    )
    (net (code "40") (name "Net-(VD3-Cathode)") (class "Default")
      (node (ref "R10") (pin "1") (pinfunction "1_1") (pintype "passive"))
      (node (ref "R11") (pin "1") (pinfunction "1_1") (pintype "passive"))
      (node (ref "VD3") (pin "1") (pinfunction "Cathode_1") (pintype "passive"))
      (node (ref "X6") (pin "15") (pinfunction "15_15") (pintype "passive"))
    )
    (net (code "41") (name "Net-(VD4-Anode)") (class "Default")
      (node (ref "R16") (pin "2") (pinfunction "2_2") (pintype "passive"))
      (node (ref "VD4") (pin "2") (pinfunction "Anode_2") (pintype "passive"))
    )
    (net (code "42") (name "Net-(VD4-Cathode)") (class "Default")
      (node (ref "R17") (pin "1") (pinfunction "1_1") (pintype "passive"))
      (node (ref "R18") (pin "1") (pinfunction "1_1") (pintype "passive"))
      (node (ref "VD4") (pin "1") (pinfunction "Cathode_1") (pintype "passive"))
      (node (ref "X7") (pin "3") (pinfunction "3_3") (pintype "passive"))
    )
    (net (code "43") (name "Net-(VD5-Anode)") (class "Default")
      (node (ref "R20") (pin "2") (pinfunction "2_2") (pintype "passive"))
      (node (ref "VD5") (pin "2") (pinfunction "Anode_2") (pintype "passive"))
    )
    (net (code "44") (name "Net-(VD5-Cathode)") (class "Default")
      (node (ref "R21") (pin "1") (pinfunction "1_1") (pintype "passive"))
      (node (ref "R22") (pin "1") (pinfunction "1_1") (pintype "passive"))
      (node (ref "VD5") (pin "1") (pinfunction "Cathode_1") (pintype "passive"))
      (node (ref "X7") (pin "9") (pinfunction "9_9") (pintype "passive"))
    )
    (net (code "45") (name "Net-(VD6-Anode)") (class "Default")
      (node (ref "R24") (pin "2") (pinfunction "2_2") (pintype "passive"))
      (node (ref "VD6") (pin "2") (pinfunction "Anode_2") (pintype "passive"))
    )
    (net (code "46") (name "Net-(VD6-Cathode)") (class "Default")
      (node (ref "R25") (pin "1") (pinfunction "1_1") (pintype "passive"))
      (node (ref "R26") (pin "1") (pinfunction "1_1") (pintype "passive"))
      (node (ref "VD6") (pin "1") (pinfunction "Cathode_1") (pintype "passive"))
      (node (ref "X7") (pin "15") (pinfunction "15_15") (pintype "passive"))
    )
    (net (code "47") (name "Net-(VD7-Anode)") (class "Default")
      (node (ref "R31") (pin "2") (pinfunction "2_2") (pintype "passive"))
      (node (ref "VD7") (pin "2") (pinfunction "Anode_2") (pintype "passive"))
    )
    (net (code "48") (name "Net-(VD7-Cathode)") (class "Default")
      (node (ref "R32") (pin "1") (pinfunction "1_1") (pintype "passive"))
      (node (ref "R33") (pin "1") (pinfunction "1_1") (pintype "passive"))
      (node (ref "VD7") (pin "1") (pinfunction "Cathode_1") (pintype "passive"))
      (node (ref "X8") (pin "3") (pinfunction "3_3") (pintype "passive"))
    )
    (net (code "49") (name "Net-(VD8-Anode)") (class "Default")
      (node (ref "R35") (pin "2") (pinfunction "2_2") (pintype "passive"))
      (node (ref "VD8") (pin "2") (pinfunction "Anode_2") (pintype "passive"))
    )
    (net (code "50") (name "Net-(VD8-Cathode)") (class "Default")
      (node (ref "R36") (pin "1") (pinfunction "1_1") (pintype "passive"))
      (node (ref "R37") (pin "1") (pinfunction "1_1") (pintype "passive"))
      (node (ref "VD8") (pin "1") (pinfunction "Cathode_1") (pintype "passive"))
      (node (ref "X8") (pin "9") (pinfunction "9_9") (pintype "passive"))
    )
    (net (code "51") (name "Net-(VD9-Anode)") (class "Default")
      (node (ref "R39") (pin "2") (pinfunction "2_2") (pintype "passive"))
      (node (ref "VD9") (pin "2") (pinfunction "Anode_2") (pintype "passive"))
    )
    (net (code "52") (name "Net-(VD9-Cathode)") (class "Default")
      (node (ref "R40") (pin "1") (pinfunction "1_1") (pintype "passive"))
      (node (ref "R41") (pin "1") (pinfunction "1_1") (pintype "passive"))
      (node (ref "VD9") (pin "1") (pinfunction "Cathode_1") (pintype "passive"))
      (node (ref "X8") (pin "15") (pinfunction "15_15") (pintype "passive"))
    )
    (net (code "53") (name "Net-(X1-Pad2)") (class "Default")
      (node (ref "X1") (pin "2") (pinfunction "2_2") (pintype "passive"))
      (node (ref "X6") (pin "1") (pinfunction "1_1") (pintype "passive"))
      (node (ref "X6") (pin "6") (pinfunction "6_6") (pintype "passive"))
    )
    (net (code "54") (name "Net-(X1-Pad3)") (class "Default")
      (node (ref "X1") (pin "3") (pinfunction "3_3") (pintype "passive"))
      (node (ref "X6") (pin "12") (pinfunction "12_12") (pintype "passive"))
      (node (ref "X6") (pin "7") (pinfunction "7_7") (pintype "passive"))
    )
    (net (code "55") (name "Net-(X1-Pad4)") (class "Default")
      (node (ref "X1") (pin "4") (pinfunction "4_4") (pintype "passive"))
      (node (ref "X6") (pin "13") (pinfunction "13_13") (pintype "passive"))
      (node (ref "X6") (pin "18") (pinfunction "18_18") (pintype "passive"))
    )
    (net (code "56") (name "Net-(X2-Pad2)") (class "Default")
      (node (ref "X2") (pin "2") (pinfunction "2_2") (pintype "passive"))
      (node (ref "X7") (pin "1") (pinfunction "1_1") (pintype "passive"))
      (node (ref "X7") (pin "6") (pinfunction "6_6") (pintype "passive"))
    )
    (net (code "57") (name "Net-(X2-Pad3)") (class "Default")
      (node (ref "X2") (pin "3") (pinfunction "3_3") (pintype "passive"))
      (node (ref "X7") (pin "12") (pinfunction "12_12") (pintype "passive"))
      (node (ref "X7") (pin "7") (pinfunction "7_7") (pintype "passive"))
    )
    (net (code "58") (name "Net-(X2-Pad4)") (class "Default")
      (node (ref "X2") (pin "4") (pinfunction "4_4") (pintype "passive"))
      (node (ref "X7") (pin "13") (pinfunction "13_13") (pintype "passive"))
      (node (ref "X7") (pin "18") (pinfunction "18_18") (pintype "passive"))
    )
    (net (code "59") (name "Net-(X3-Pad2)") (class "Default")
      (node (ref "X3") (pin "2") (pinfunction "2_2") (pintype "passive"))
      (node (ref "X8") (pin "1") (pinfunction "1_1") (pintype "passive"))
      (node (ref "X8") (pin "6") (pinfunction "6_6") (pintype "passive"))
    )
    (net (code "60") (name "Net-(X3-Pad3)") (class "Default")
      (node (ref "X3") (pin "3") (pinfunction "3_3") (pintype "passive"))
      (node (ref "X8") (pin "12") (pinfunction "12_12") (pintype "passive"))
      (node (ref "X8") (pin "7") (pinfunction "7_7") (pintype "passive"))
    )
    (net (code "61") (name "Net-(X3-Pad4)") (class "Default")
      (node (ref "X3") (pin "4") (pinfunction "4_4") (pintype "passive"))
      (node (ref "X8") (pin "13") (pinfunction "13_13") (pintype "passive"))
      (node (ref "X8") (pin "18") (pinfunction "18_18") (pintype "passive"))
    )
  )
)
